# Sensor.net
KiCad netlist of a schematic drawn in EAGLE
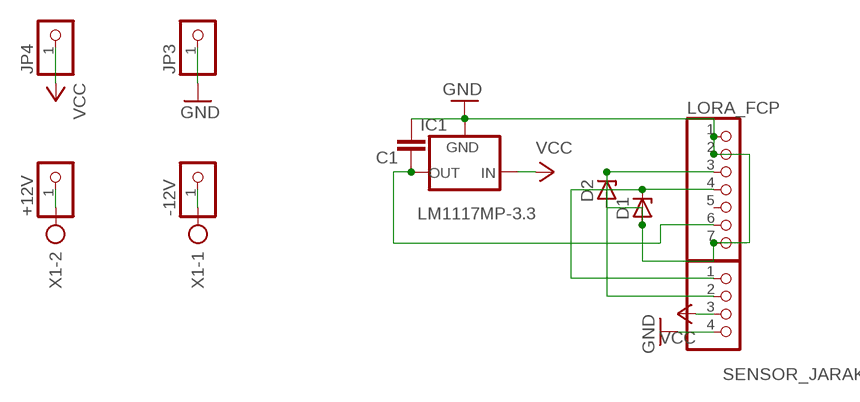
[diagram p0: schematic, sheet 1]

(export (version "E")
  (design (tool "Eeschema 10.0.6"))
  (components
    (comp (ref "+12V")
      (value "PINHD-1X1")
      (footprint "eagle-import:1X01")
      (libsource (lib "eagle-import") (part "PINHD-1X1"))
    )
    (comp (ref "-12V")
      (value "PINHD-1X1")
      (footprint "eagle-import:1X01")
      (libsource (lib "eagle-import") (part "PINHD-1X1"))
    )
    (comp (ref "C1")
      (value "C-EU025-024X044")
      (footprint "eagle-import:C025-024X044")
      (libsource (lib "eagle-import") (part "C-EU025-024X044"))
    )
    (comp (ref "D1")
      (value "ZENER-DIODEDO35Z10")
      (footprint "eagle-import:DO35Z10")
      (libsource (lib "eagle-import") (part "ZENER-DIODEDO35Z10"))
    )
    (comp (ref "D2")
      (value "ZENER-DIODEDO35Z10")
      (footprint "eagle-import:DO35Z10")
      (libsource (lib "eagle-import") (part "ZENER-DIODEDO35Z10"))
    )
    (comp (ref "IC1")
      (value "LM1117MP-3.3")
      (footprint "eagle-import:SOT223")
      (fields (field (name "MF") "Texas Instruments"))
      (libsource (lib "eagle-import") (part "LM1117?-MP3.3"))
    )
    (comp (ref "JP3")
      (value "PINHD-1X1")
      (footprint "eagle-import:1X01")
      (libsource (lib "eagle-import") (part "PINHD-1X1"))
    )
    (comp (ref "JP4")
      (value "PINHD-1X1")
      (footprint "eagle-import:1X01")
      (libsource (lib "eagle-import") (part "PINHD-1X1"))
    )
    (comp (ref "LORA_FCP")
      (value "PINHD-1X7")
      (footprint "eagle-import:1X07")
      (libsource (lib "eagle-import") (part "PINHD-1X7"))
    )
    (comp (ref "SENSOR_JARAK")
      (value "PINHD-1X4")
      (footprint "eagle-import:1X04")
      (libsource (lib "eagle-import") (part "PINHD-1X4"))
    )
    (comp (ref "X1")
      (value "AK300/2")
      (footprint "eagle-import:AK300_2")
      (libsource (lib "eagle-import") (part "AK300/2"))
    )
  )
  (nets
    (net (code "1") (name "GND") (class "Default")
      (node (ref "C1") (pin "1") (pinfunction "1_1") (pintype "passive"))
      (node (ref "D1") (pin "A") (pinfunction "A_A") (pintype "passive"))
      (node (ref "D2") (pin "A") (pinfunction "A_A") (pintype "passive"))
      (node (ref "IC1") (pin "1") (pinfunction "GND_1") (pintype "input"))
      (node (ref "JP3") (pin "1") (pinfunction "1_1") (pintype "passive"))
      (node (ref "LORA_FCP") (pin "1") (pinfunction "1_1") (pintype "passive"))
      (node (ref "LORA_FCP") (pin "2") (pinfunction "2_2") (pintype "passive"))
      (node (ref "LORA_FCP") (pin "7") (pinfunction "7_7") (pintype "passive"))
      (node (ref "SENSOR_JARAK") (pin "4") (pinfunction "4_4") (pintype "passive"))
    )
    (net (code "2") (name "Net-(C1-Pad2)") (class "Default")
      (node (ref "C1") (pin "2") (pinfunction "2_2") (pintype "passive"))
      (node (ref "IC1") (pin "2") (pinfunction "OUT_2") (pintype "passive"))
      (node (ref "IC1") (pin "4") (pinfunction "OUT_4") (pintype "passive"))
      (node (ref "LORA_FCP") (pin "6") (pinfunction "6_6") (pintype "passive"))
    )
    (net (code "3") (name "Net-(D1-PadC)") (class "Default")
      (node (ref "D1") (pin "C") (pinfunction "C_C") (pintype "passive"))
      (node (ref "LORA_FCP") (pin "4") (pinfunction "4_4") (pintype "passive"))
      (node (ref "SENSOR_JARAK") (pin "1") (pinfunction "1_1") (pintype "passive"))
    )
    (net (code "4") (name "Net-(D2-PadC)") (class "Default")
      (node (ref "D2") (pin "C") (pinfunction "C_C") (pintype "passive"))
      (node (ref "LORA_FCP") (pin "3") (pinfunction "3_3") (pintype "passive"))
      (node (ref "SENSOR_JARAK") (pin "2") (pinfunction "2_2") (pintype "passive"))
    )
    (net (code "5") (name "Net-(X1A-KL)") (class "Default")
      (node (ref "-12V") (pin "1") (pinfunction "1_1") (pintype "passive"))
      (node (ref "X1") (pin "1") (pinfunction "KL_1") (pintype "passive"))
    )
    (net (code "6") (name "Net-(X1B-KL)") (class "Default")
      (node (ref "+12V") (pin "1") (pinfunction "1_1") (pintype "passive"))
      (node (ref "X1") (pin "2") (pinfunction "KL_2") (pintype "passive"))
    )
    (net (code "7") (name "VCC") (class "Default")
      (node (ref "IC1") (pin "3") (pinfunction "IN_3") (pintype "input"))
      (node (ref "JP4") (pin "1") (pinfunction "1_1") (pintype "passive"))
      (node (ref "SENSOR_JARAK") (pin "3") (pinfunction "3_3") (pintype "passive"))
    )
    (net (code "8") (name "unconnected-(LORA_FCP-Pad5)") (class "Default")
      (node (ref "LORA_FCP") (pin "5") (pinfunction "5_5") (pintype "passive"))
    )
  )
)
